# connectors.net
KiCad netlist of a schematic drawn in EAGLE
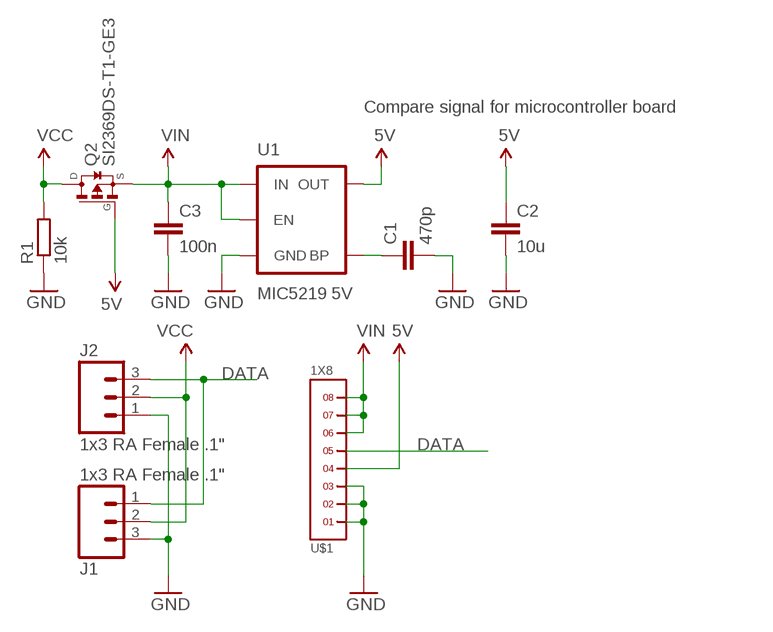
[diagram p0: schematic, sheet 1]

(export (version "E")
  (design (tool "Eeschema 10.0.6"))
  (components
    (comp (ref "C1")
      (value "470p")
      (footprint "eagle-import:C0402K")
      (libsource (lib "eagle-import") (part "C-EUC0402K"))
    )
    (comp (ref "C2")
      (value "10u")
      (footprint "eagle-import:C0603K")
      (libsource (lib "eagle-import") (part "C-EUC0603K"))
    )
    (comp (ref "C3")
      (value "100n")
      (footprint "eagle-import:C0402K")
      (libsource (lib "eagle-import") (part "C-EUC0402K"))
    )
    (comp (ref "J1")
      (value "1x3 RA Female .1\"")
      (footprint "eagle-import:1X03_SMD_RA_FEMALE")
      (libsource (lib "eagle-import") (part "M03SMD_RA_FEMALE"))
    )
    (comp (ref "J2")
      (value "1x3 RA Female .1\"")
      (footprint "eagle-import:1X03_SMD_RA_FEMALE")
      (libsource (lib "eagle-import") (part "M03SMD_RA_FEMALE"))
    )
    (comp (ref "Q2")
      (value "SI2369DS-T1-GE3")
      (footprint "eagle-import:SOT23")
      (libsource (lib "eagle-import") (part "SI2333DS"))
    )
    (comp (ref "R1")
      (value "10k")
      (footprint "eagle-import:R0603")
      (libsource (lib "eagle-import") (part "R-EU_R0603"))
    )
    (comp (ref "U$1")
      (value "1X8")
      (footprint "eagle-import:1X8")
      (libsource (lib "eagle-import") (part "1X8"))
    )
    (comp (ref "U1")
      (value "MIC5219 5V")
      (footprint "eagle-import:SOT23-5")
      (libsource (lib "eagle-import") (part "V_REG_MIC52195V"))
    )
  )
  (nets
    (net (code "1") (name "/DATA") (class "Default")
      (node (ref "J1") (pin "1") (pinfunction "1_1") (pintype "passive"))
      (node (ref "J2") (pin "3") (pinfunction "3_3") (pintype "passive"))
      (node (ref "U$1") (pin "5") (pinfunction "5_5") (pintype "bidirectional"))
    )
    (net (code "2") (name "5V") (class "Default")
      (node (ref "C2") (pin "1") (pinfunction "1_1") (pintype "passive"))
      (node (ref "Q2") (pin "1") (pinfunction "G_1") (pintype "passive"))
      (node (ref "U$1") (pin "4") (pinfunction "4_4") (pintype "bidirectional"))
      (node (ref "U1") (pin "5") (pinfunction "OUT_5") (pintype "passive"))
    )
    (net (code "3") (name "GND") (class "Default")
      (node (ref "C1") (pin "2") (pinfunction "2_2") (pintype "passive"))
      (node (ref "C2") (pin "2") (pinfunction "2_2") (pintype "passive"))
      (node (ref "C3") (pin "2") (pinfunction "2_2") (pintype "passive"))
      (node (ref "J1") (pin "3") (pinfunction "3_3") (pintype "passive"))
      (node (ref "J2") (pin "1") (pinfunction "1_1") (pintype "passive"))
      (node (ref "R1") (pin "1") (pinfunction "1_1") (pintype "passive"))
      (node (ref "U$1") (pin "1") (pinfunction "1_1") (pintype "bidirectional"))
      (node (ref "U$1") (pin "2") (pinfunction "2_2") (pintype "bidirectional"))
      (node (ref "U$1") (pin "3") (pinfunction "3_3") (pintype "bidirectional"))
      (node (ref "U1") (pin "2") (pinfunction "GND_2") (pintype "input"))
    )
    (net (code "4") (name "Net-(U1-BP)") (class "Default")
      (node (ref "C1") (pin "1") (pinfunction "1_1") (pintype "passive"))
      (node (ref "U1") (pin "4") (pinfunction "BP_4") (pintype "input"))
    )
    (net (code "5") (name "VCC") (class "Default")
      (node (ref "J1") (pin "2") (pinfunction "2_2") (pintype "passive"))
      (node (ref "J2") (pin "2") (pinfunction "2_2") (pintype "passive"))
      (node (ref "Q2") (pin "3") (pinfunction "D_3") (pintype "passive"))
      (node (ref "R1") (pin "2") (pinfunction "2_2") (pintype "passive"))
    )
    (net (code "6") (name "VIN") (class "Default")
      (node (ref "C3") (pin "1") (pinfunction "1_1") (pintype "passive"))
      (node (ref "Q2") (pin "2") (pinfunction "S_2") (pintype "passive"))
      (node (ref "U$1") (pin "6") (pinfunction "6_6") (pintype "bidirectional"))
      (node (ref "U$1") (pin "7") (pinfunction "7_7") (pintype "bidirectional"))
      (node (ref "U$1") (pin "8") (pinfunction "8_8") (pintype "bidirectional"))
      (node (ref "U1") (pin "1") (pinfunction "IN_1") (pintype "input"))
      (node (ref "U1") (pin "3") (pinfunction "EN_3") (pintype "input"))
    )
  )
)
